# TM1638_10.net
KiCad netlist of a schematic drawn in Altium Designer
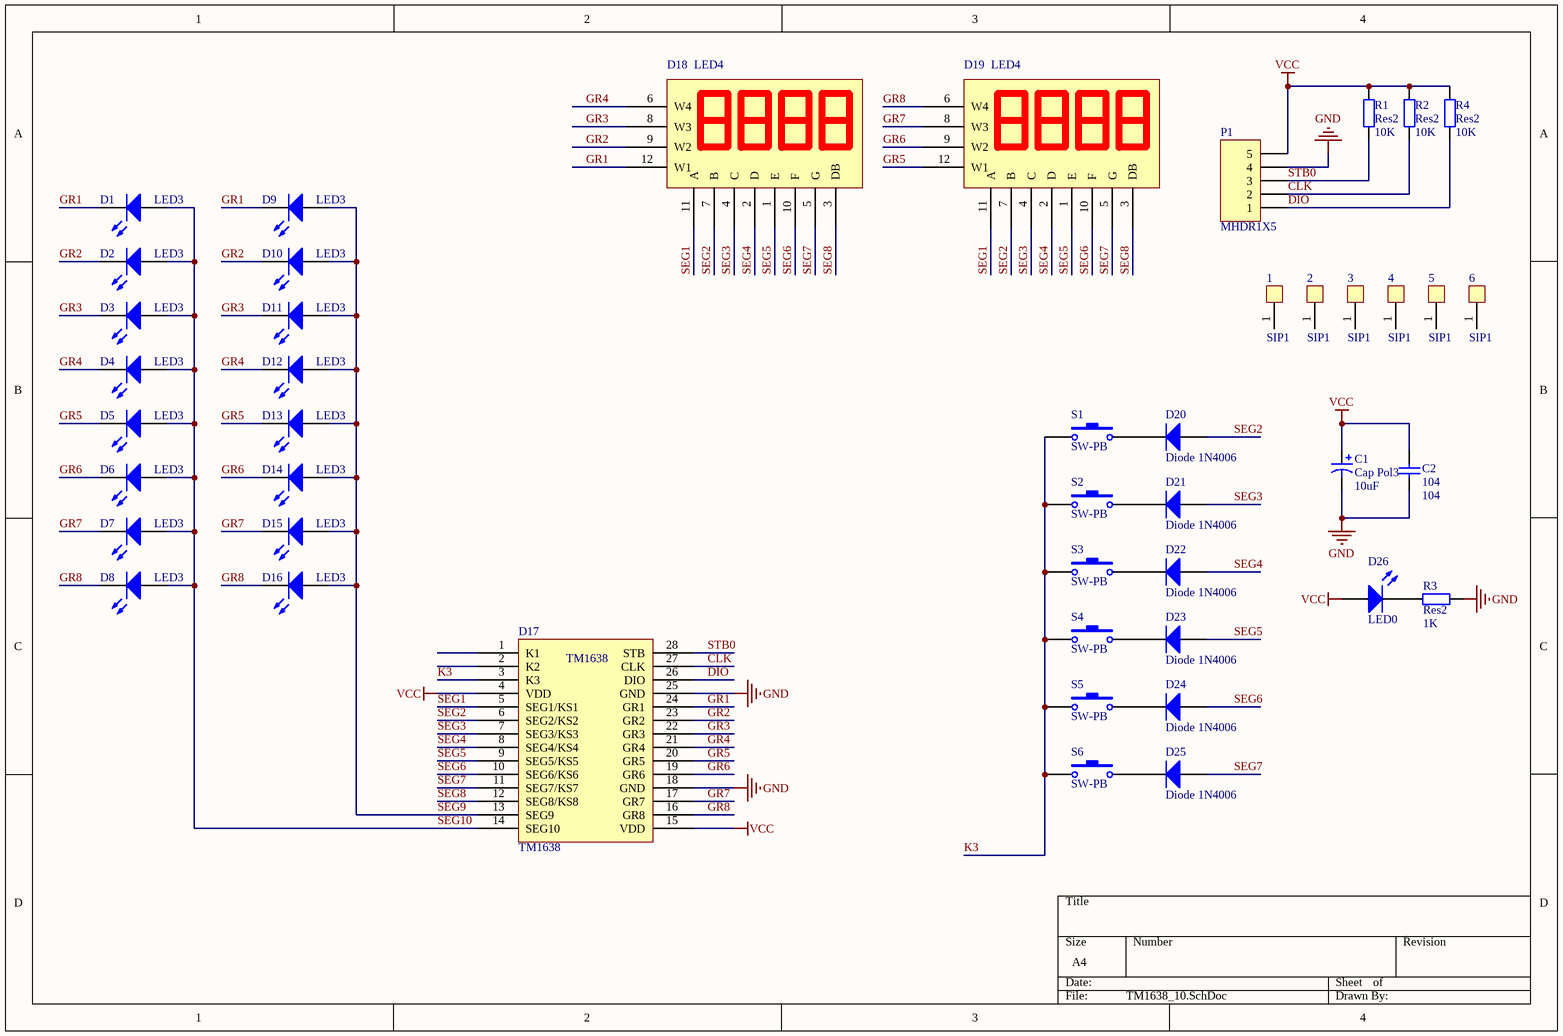
[diagram p0: TM1638_10.SchDoc]

(export (version "E")
  (design (tool "Eeschema 10.0.6"))
  (components
    (comp (ref "1")
      (value "SIP1")
      (footprint "hole")
      (description "Variable Resistor")
      (fields (field (name "PUBLISHER") "Altium Limited"))
      (libsource (lib "jointbar") (part "SIP1"))
    )
    (comp (ref "2")
      (value "SIP1")
      (footprint "hole")
      (description "Variable Resistor")
      (fields (field (name "PUBLISHER") "Altium Limited"))
      (libsource (lib "jointbar") (part "SIP1"))
    )
    (comp (ref "3")
      (value "SIP1")
      (footprint "hole")
      (description "Variable Resistor")
      (fields (field (name "PUBLISHER") "Altium Limited"))
      (libsource (lib "jointbar") (part "SIP1"))
    )
    (comp (ref "4")
      (value "SIP1")
      (footprint "hole")
      (description "Variable Resistor")
      (fields (field (name "PUBLISHER") "Altium Limited"))
      (libsource (lib "jointbar") (part "SIP1"))
    )
    (comp (ref "5")
      (value "SIP1")
      (footprint "hole")
      (description "Variable Resistor")
      (fields (field (name "PUBLISHER") "Altium Limited"))
      (libsource (lib "jointbar") (part "SIP1"))
    )
    (comp (ref "6")
      (value "SIP1")
      (footprint "hole")
      (description "Variable Resistor")
      (fields (field (name "PUBLISHER") "Altium Limited"))
      (libsource (lib "jointbar") (part "SIP1"))
    )
    (comp (ref "C1")
      (value "Cap Pol3")
      (footprint "0805")
      (description "Polarized Capacitor (Surface Mount)")
      (fields (field (name "ALTIUM_VALUE") "10uF") (field (name "PUBLISHER") "Altium Limited"))
      (libsource (lib "Miscellaneous Devices") (part "Cap Pol3"))
    )
    (comp (ref "C2")
      (value "104")
      (footprint "0805")
      (description "Capacitor (Semiconductor SIM Model)")
      (fields (field (name "ALTIUM_VALUE") "104") (field (name "PUBLISHER") "Altium Limited"))
      (libsource (lib "Miscellaneous Devices") (part "Cap Semi"))
    )
    (comp (ref "D1")
      (value "LED3")
      (footprint "LED0")
      (description "Typical BLUE SiC LED")
      (fields (field (name "PUBLISHER") "Altium Limited"))
      (libsource (lib "Miscellaneous Devices") (part "LED3"))
    )
    (comp (ref "D2")
      (value "LED3")
      (footprint "LED0")
      (description "Typical BLUE SiC LED")
      (fields (field (name "PUBLISHER") "Altium Limited"))
      (libsource (lib "Miscellaneous Devices") (part "LED3"))
    )
    (comp (ref "D3")
      (value "LED3")
      (footprint "LED0")
      (description "Typical BLUE SiC LED")
      (fields (field (name "PUBLISHER") "Altium Limited"))
      (libsource (lib "Miscellaneous Devices") (part "LED3"))
    )
    (comp (ref "D4")
      (value "LED3")
      (footprint "LED0")
      (description "Typical BLUE SiC LED")
      (fields (field (name "PUBLISHER") "Altium Limited"))
      (libsource (lib "Miscellaneous Devices") (part "LED3"))
    )
    (comp (ref "D5")
      (value "LED3")
      (footprint "LED0")
      (description "Typical BLUE SiC LED")
      (fields (field (name "PUBLISHER") "Altium Limited"))
      (libsource (lib "Miscellaneous Devices") (part "LED3"))
    )
    (comp (ref "D6")
      (value "LED3")
      (footprint "LED0")
      (description "Typical BLUE SiC LED")
      (fields (field (name "PUBLISHER") "Altium Limited"))
      (libsource (lib "Miscellaneous Devices") (part "LED3"))
    )
    (comp (ref "D7")
      (value "LED3")
      (footprint "LED0")
      (description "Typical BLUE SiC LED")
      (fields (field (name "PUBLISHER") "Altium Limited"))
      (libsource (lib "Miscellaneous Devices") (part "LED3"))
    )
    (comp (ref "D8")
      (value "LED3")
      (footprint "LED0")
      (description "Typical BLUE SiC LED")
      (fields (field (name "PUBLISHER") "Altium Limited"))
      (libsource (lib "Miscellaneous Devices") (part "LED3"))
    )
    (comp (ref "D9")
      (value "LED3")
      (footprint "LED0")
      (description "Typical BLUE SiC LED")
      (fields (field (name "PUBLISHER") "Altium Limited"))
      (libsource (lib "Miscellaneous Devices") (part "LED3"))
    )
    (comp (ref "D10")
      (value "LED3")
      (footprint "LED0")
      (description "Typical BLUE SiC LED")
      (fields (field (name "PUBLISHER") "Altium Limited"))
      (libsource (lib "Miscellaneous Devices") (part "LED3"))
    )
    (comp (ref "D11")
      (value "LED3")
      (footprint "LED0")
      (description "Typical BLUE SiC LED")
      (fields (field (name "PUBLISHER") "Altium Limited"))
      (libsource (lib "Miscellaneous Devices") (part "LED3"))
    )
    (comp (ref "D12")
      (value "LED3")
      (footprint "LED0")
      (description "Typical BLUE SiC LED")
      (fields (field (name "PUBLISHER") "Altium Limited"))
      (libsource (lib "Miscellaneous Devices") (part "LED3"))
    )
    (comp (ref "D13")
      (value "LED3")
      (footprint "LED0")
      (description "Typical BLUE SiC LED")
      (fields (field (name "PUBLISHER") "Altium Limited"))
      (libsource (lib "Miscellaneous Devices") (part "LED3"))
    )
    (comp (ref "D14")
      (value "LED3")
      (footprint "LED0")
      (description "Typical BLUE SiC LED")
      (fields (field (name "PUBLISHER") "Altium Limited"))
      (libsource (lib "Miscellaneous Devices") (part "LED3"))
    )
    (comp (ref "D15")
      (value "LED3")
      (footprint "LED0")
      (description "Typical BLUE SiC LED")
      (fields (field (name "PUBLISHER") "Altium Limited"))
      (libsource (lib "Miscellaneous Devices") (part "LED3"))
    )
    (comp (ref "D16")
      (value "LED3")
      (footprint "LED0")
      (description "Typical BLUE SiC LED")
      (fields (field (name "PUBLISHER") "Altium Limited"))
      (libsource (lib "Miscellaneous Devices") (part "LED3"))
    )
    (comp (ref "D17") (value "TM1638") (footprint "SOP28") (libsource (lib "AD620") (part "TM1638")))
    (comp (ref "D18") (value "LED4") (footprint "LED4") (libsource (lib "AD620") (part "LED_N4")))
    (comp (ref "D19") (value "LED4") (footprint "LED4") (libsource (lib "AD620") (part "LED_N4")))
    (comp (ref "D20")
      (value "Diode 1N4006")
      (footprint "1N4148")
      (description "1 Amp General Purpose Rectifier")
      (fields (field (name "PUBLISHER") "Altium Limited"))
      (libsource (lib "Miscellaneous Devices") (part "Diode 1N4006"))
    )
    (comp (ref "D21")
      (value "Diode 1N4006")
      (footprint "1N4148")
      (description "1 Amp General Purpose Rectifier")
      (fields (field (name "PUBLISHER") "Altium Limited"))
      (libsource (lib "Miscellaneous Devices") (part "Diode 1N4006"))
    )
    (comp (ref "D22")
      (value "Diode 1N4006")
      (footprint "1N4148")
      (description "1 Amp General Purpose Rectifier")
      (fields (field (name "PUBLISHER") "Altium Limited"))
      (libsource (lib "Miscellaneous Devices") (part "Diode 1N4006"))
    )
    (comp (ref "D23")
      (value "Diode 1N4006")
      (footprint "1N4148")
      (description "1 Amp General Purpose Rectifier")
      (fields (field (name "PUBLISHER") "Altium Limited"))
      (libsource (lib "Miscellaneous Devices") (part "Diode 1N4006"))
    )
    (comp (ref "D24")
      (value "Diode 1N4006")
      (footprint "1N4148")
      (description "1 Amp General Purpose Rectifier")
      (fields (field (name "PUBLISHER") "Altium Limited"))
      (libsource (lib "Miscellaneous Devices") (part "Diode 1N4006"))
    )
    (comp (ref "D25")
      (value "Diode 1N4006")
      (footprint "1N4148")
      (description "1 Amp General Purpose Rectifier")
      (fields (field (name "PUBLISHER") "Altium Limited"))
      (libsource (lib "Miscellaneous Devices") (part "Diode 1N4006"))
    )
    (comp (ref "D26")
      (value "LED0")
      (footprint "LED0")
      (description "Typical INFRARED GaAs LED")
      (fields (field (name "PUBLISHER") "Altium Limited"))
      (libsource (lib "Miscellaneous Devices") (part "LED0"))
    )
    (comp (ref "P1")
      (value "MHDR1X5")
      (footprint "CON5")
      (description "Header, 5-Pin")
      (fields (field (name "PUBLISHER") "Altium Limited"))
      (libsource (lib "Miscellaneous Connectors") (part "MHDR1X5"))
    )
    (comp (ref "R1")
      (value "Res2")
      (footprint "0805")
      (description "Resistor")
      (fields (field (name "ALTIUM_VALUE") "10K") (field (name "PUBLISHER") "Altium Limited"))
      (libsource (lib "Miscellaneous Devices") (part "Res2"))
    )
    (comp (ref "R2")
      (value "Res2")
      (footprint "0805")
      (description "Resistor")
      (fields (field (name "ALTIUM_VALUE") "10K") (field (name "PUBLISHER") "Altium Limited"))
      (libsource (lib "Miscellaneous Devices") (part "Res2"))
    )
    (comp (ref "R3")
      (value "Res2")
      (footprint "0805")
      (description "Resistor")
      (fields (field (name "ALTIUM_VALUE") "1K") (field (name "PUBLISHER") "Altium Limited"))
      (libsource (lib "") (part "Res2_1"))
    )
    (comp (ref "R4")
      (value "Res2")
      (footprint "0805")
      (description "Resistor")
      (fields (field (name "ALTIUM_VALUE") "10K") (field (name "PUBLISHER") "Altium Limited"))
      (libsource (lib "Miscellaneous Devices") (part "Res2"))
    )
    (comp (ref "S1")
      (value "SW-PB")
      (footprint "key")
      (description "Switch")
      (fields (field (name "PUBLISHER") "Altium Limited"))
      (libsource (lib "Miscellaneous Devices") (part "SW-PB"))
    )
    (comp (ref "S2")
      (value "SW-PB")
      (footprint "key")
      (description "Switch")
      (fields (field (name "PUBLISHER") "Altium Limited"))
      (libsource (lib "Miscellaneous Devices") (part "SW-PB"))
    )
    (comp (ref "S3")
      (value "SW-PB")
      (footprint "key")
      (description "Switch")
      (fields (field (name "PUBLISHER") "Altium Limited"))
      (libsource (lib "Miscellaneous Devices") (part "SW-PB"))
    )
    (comp (ref "S4")
      (value "SW-PB")
      (footprint "key")
      (description "Switch")
      (fields (field (name "PUBLISHER") "Altium Limited"))
      (libsource (lib "Miscellaneous Devices") (part "SW-PB"))
    )
    (comp (ref "S5")
      (value "SW-PB")
      (footprint "key")
      (description "Switch")
      (fields (field (name "PUBLISHER") "Altium Limited"))
      (libsource (lib "Miscellaneous Devices") (part "SW-PB"))
    )
    (comp (ref "S6")
      (value "SW-PB")
      (footprint "key")
      (description "Switch")
      (fields (field (name "PUBLISHER") "Altium Limited"))
      (libsource (lib "Miscellaneous Devices") (part "SW-PB"))
    )
  )
  (nets
    (net (code "1") (name "/CLK") (class "Default")
      (node (ref "D17") (pin "27") (pinfunction "CLK_27") (pintype "passive"))
      (node (ref "P1") (pin "2") (pinfunction "2_2") (pintype "passive"))
      (node (ref "R2") (pin "1") (pinfunction "1_1") (pintype "passive"))
    )
    (net (code "2") (name "/DIO") (class "Default")
      (node (ref "D17") (pin "26") (pinfunction "DIO_26") (pintype "passive"))
      (node (ref "P1") (pin "1") (pinfunction "1_1") (pintype "passive"))
      (node (ref "R4") (pin "1") (pinfunction "1_1") (pintype "passive"))
    )
    (net (code "3") (name "/GR1") (class "Default")
      (node (ref "D1") (pin "2") (pinfunction "K_2") (pintype "passive"))
      (node (ref "D17") (pin "24") (pinfunction "GR1_24") (pintype "passive"))
      (node (ref "D18") (pin "12") (pinfunction "W1_12") (pintype "passive"))
      (node (ref "D9") (pin "2") (pinfunction "K_2") (pintype "passive"))
    )
    (net (code "4") (name "/GR2") (class "Default")
      (node (ref "D10") (pin "2") (pinfunction "K_2") (pintype "passive"))
      (node (ref "D17") (pin "23") (pinfunction "GR2_23") (pintype "passive"))
      (node (ref "D18") (pin "9") (pinfunction "W2_9") (pintype "passive"))
      (node (ref "D2") (pin "2") (pinfunction "K_2") (pintype "passive"))
    )
    (net (code "5") (name "/GR3") (class "Default")
      (node (ref "D11") (pin "2") (pinfunction "K_2") (pintype "passive"))
      (node (ref "D17") (pin "22") (pinfunction "GR3_22") (pintype "passive"))
      (node (ref "D18") (pin "8") (pinfunction "W3_8") (pintype "passive"))
      (node (ref "D3") (pin "2") (pinfunction "K_2") (pintype "passive"))
    )
    (net (code "6") (name "/GR4") (class "Default")
      (node (ref "D12") (pin "2") (pinfunction "K_2") (pintype "passive"))
      (node (ref "D17") (pin "21") (pinfunction "GR4_21") (pintype "passive"))
      (node (ref "D18") (pin "6") (pinfunction "W4_6") (pintype "passive"))
      (node (ref "D4") (pin "2") (pinfunction "K_2") (pintype "passive"))
    )
    (net (code "7") (name "/GR5") (class "Default")
      (node (ref "D13") (pin "2") (pinfunction "K_2") (pintype "passive"))
      (node (ref "D17") (pin "20") (pinfunction "GR5_20") (pintype "passive"))
      (node (ref "D19") (pin "12") (pinfunction "W1_12") (pintype "passive"))
      (node (ref "D5") (pin "2") (pinfunction "K_2") (pintype "passive"))
    )
    (net (code "8") (name "/GR6") (class "Default")
      (node (ref "D14") (pin "2") (pinfunction "K_2") (pintype "passive"))
      (node (ref "D17") (pin "19") (pinfunction "GR6_19") (pintype "passive"))
      (node (ref "D19") (pin "9") (pinfunction "W2_9") (pintype "passive"))
      (node (ref "D6") (pin "2") (pinfunction "K_2") (pintype "passive"))
    )
    (net (code "9") (name "/GR7") (class "Default")
      (node (ref "D15") (pin "2") (pinfunction "K_2") (pintype "passive"))
      (node (ref "D17") (pin "17") (pinfunction "GR7_17") (pintype "passive"))
      (node (ref "D19") (pin "8") (pinfunction "W3_8") (pintype "passive"))
      (node (ref "D7") (pin "2") (pinfunction "K_2") (pintype "passive"))
    )
    (net (code "10") (name "/GR8") (class "Default")
      (node (ref "D16") (pin "2") (pinfunction "K_2") (pintype "passive"))
      (node (ref "D17") (pin "16") (pinfunction "GR8_16") (pintype "passive"))
      (node (ref "D19") (pin "6") (pinfunction "W4_6") (pintype "passive"))
      (node (ref "D8") (pin "2") (pinfunction "K_2") (pintype "passive"))
    )
    (net (code "11") (name "/K3") (class "Default")
      (node (ref "D17") (pin "3") (pinfunction "K3_3") (pintype "passive"))
      (node (ref "S1") (pin "1") (pinfunction "1_1") (pintype "passive"))
      (node (ref "S2") (pin "1") (pinfunction "1_1") (pintype "passive"))
      (node (ref "S3") (pin "1") (pinfunction "1_1") (pintype "passive"))
      (node (ref "S4") (pin "1") (pinfunction "1_1") (pintype "passive"))
      (node (ref "S5") (pin "1") (pinfunction "1_1") (pintype "passive"))
      (node (ref "S6") (pin "1") (pinfunction "1_1") (pintype "passive"))
    )
    (net (code "12") (name "/SEG1") (class "Default")
      (node (ref "D17") (pin "5") (pinfunction "SEG1/KS1_5") (pintype "passive"))
      (node (ref "D18") (pin "11") (pinfunction "A_11") (pintype "passive"))
      (node (ref "D19") (pin "11") (pinfunction "A_11") (pintype "passive"))
    )
    (net (code "13") (name "/SEG2") (class "Default")
      (node (ref "D17") (pin "6") (pinfunction "SEG2/KS2_6") (pintype "passive"))
      (node (ref "D18") (pin "7") (pinfunction "B_7") (pintype "passive"))
      (node (ref "D19") (pin "7") (pinfunction "B_7") (pintype "passive"))
      (node (ref "D20") (pin "1") (pinfunction "A_1") (pintype "passive"))
    )
    (net (code "14") (name "/SEG3") (class "Default")
      (node (ref "D17") (pin "7") (pinfunction "SEG3/KS3_7") (pintype "passive"))
      (node (ref "D18") (pin "4") (pinfunction "C_4") (pintype "passive"))
      (node (ref "D19") (pin "4") (pinfunction "C_4") (pintype "passive"))
      (node (ref "D21") (pin "1") (pinfunction "A_1") (pintype "passive"))
    )
    (net (code "15") (name "/SEG4") (class "Default")
      (node (ref "D17") (pin "8") (pinfunction "SEG4/KS4_8") (pintype "passive"))
      (node (ref "D18") (pin "2") (pinfunction "D_2") (pintype "passive"))
      (node (ref "D19") (pin "2") (pinfunction "D_2") (pintype "passive"))
      (node (ref "D22") (pin "1") (pinfunction "A_1") (pintype "passive"))
    )
    (net (code "16") (name "/SEG5") (class "Default")
      (node (ref "D17") (pin "9") (pinfunction "SEG5/KS5_9") (pintype "passive"))
      (node (ref "D18") (pin "1") (pinfunction "E_1") (pintype "passive"))
      (node (ref "D19") (pin "1") (pinfunction "E_1") (pintype "passive"))
      (node (ref "D23") (pin "1") (pinfunction "A_1") (pintype "passive"))
    )
    (net (code "17") (name "/SEG6") (class "Default")
      (node (ref "D17") (pin "10") (pinfunction "SEG6/KS6_10") (pintype "passive"))
      (node (ref "D18") (pin "10") (pinfunction "F_10") (pintype "passive"))
      (node (ref "D19") (pin "10") (pinfunction "F_10") (pintype "passive"))
      (node (ref "D24") (pin "1") (pinfunction "A_1") (pintype "passive"))
    )
    (net (code "18") (name "/SEG7") (class "Default")
      (node (ref "D17") (pin "11") (pinfunction "SEG7/KS7_11") (pintype "passive"))
      (node (ref "D18") (pin "5") (pinfunction "G_5") (pintype "passive"))
      (node (ref "D19") (pin "5") (pinfunction "G_5") (pintype "passive"))
      (node (ref "D25") (pin "1") (pinfunction "A_1") (pintype "passive"))
    )
    (net (code "19") (name "/SEG8") (class "Default")
      (node (ref "D17") (pin "12") (pinfunction "SEG8/KS8_12") (pintype "passive"))
      (node (ref "D18") (pin "3") (pinfunction "DB_3") (pintype "passive"))
      (node (ref "D19") (pin "3") (pinfunction "DB_3") (pintype "passive"))
    )
    (net (code "20") (name "/SEG9") (class "Default")
      (node (ref "D10") (pin "1") (pinfunction "A_1") (pintype "passive"))
      (node (ref "D11") (pin "1") (pinfunction "A_1") (pintype "passive"))
      (node (ref "D12") (pin "1") (pinfunction "A_1") (pintype "passive"))
      (node (ref "D13") (pin "1") (pinfunction "A_1") (pintype "passive"))
      (node (ref "D14") (pin "1") (pinfunction "A_1") (pintype "passive"))
      (node (ref "D15") (pin "1") (pinfunction "A_1") (pintype "passive"))
      (node (ref "D16") (pin "1") (pinfunction "A_1") (pintype "passive"))
      (node (ref "D17") (pin "13") (pinfunction "SEG9_13") (pintype "passive"))
      (node (ref "D9") (pin "1") (pinfunction "A_1") (pintype "passive"))
    )
    (net (code "21") (name "/SEG10") (class "Default")
      (node (ref "D1") (pin "1") (pinfunction "A_1") (pintype "passive"))
      (node (ref "D17") (pin "14") (pinfunction "SEG10_14") (pintype "passive"))
      (node (ref "D2") (pin "1") (pinfunction "A_1") (pintype "passive"))
      (node (ref "D3") (pin "1") (pinfunction "A_1") (pintype "passive"))
      (node (ref "D4") (pin "1") (pinfunction "A_1") (pintype "passive"))
      (node (ref "D5") (pin "1") (pinfunction "A_1") (pintype "passive"))
      (node (ref "D6") (pin "1") (pinfunction "A_1") (pintype "passive"))
      (node (ref "D7") (pin "1") (pinfunction "A_1") (pintype "passive"))
      (node (ref "D8") (pin "1") (pinfunction "A_1") (pintype "passive"))
    )
    (net (code "22") (name "/STB0") (class "Default")
      (node (ref "D17") (pin "28") (pinfunction "STB_28") (pintype "passive"))
      (node (ref "P1") (pin "3") (pinfunction "3_3") (pintype "passive"))
      (node (ref "R1") (pin "1") (pinfunction "1_1") (pintype "passive"))
    )
    (net (code "23") (name "GND") (class "Default")
      (node (ref "C1") (pin "2") (pinfunction "2_2") (pintype "passive"))
      (node (ref "C2") (pin "1") (pinfunction "1_1") (pintype "passive"))
      (node (ref "D17") (pin "18") (pinfunction "GND_18") (pintype "passive"))
      (node (ref "D17") (pin "25") (pinfunction "GND_25") (pintype "passive"))
      (node (ref "P1") (pin "4") (pinfunction "4_4") (pintype "passive"))
      (node (ref "R3") (pin "1") (pinfunction "1_1") (pintype "passive"))
    )
    (net (code "24") (name "Net-(D20-K)") (class "Default")
      (node (ref "D20") (pin "2") (pinfunction "K_2") (pintype "passive"))
      (node (ref "S1") (pin "2") (pinfunction "2_2") (pintype "passive"))
    )
    (net (code "25") (name "Net-(D21-K)") (class "Default")
      (node (ref "D21") (pin "2") (pinfunction "K_2") (pintype "passive"))
      (node (ref "S2") (pin "2") (pinfunction "2_2") (pintype "passive"))
    )
    (net (code "26") (name "Net-(D22-K)") (class "Default")
      (node (ref "D22") (pin "2") (pinfunction "K_2") (pintype "passive"))
      (node (ref "S3") (pin "2") (pinfunction "2_2") (pintype "passive"))
    )
    (net (code "27") (name "Net-(D23-K)") (class "Default")
      (node (ref "D23") (pin "2") (pinfunction "K_2") (pintype "passive"))
      (node (ref "S4") (pin "2") (pinfunction "2_2") (pintype "passive"))
    )
    (net (code "28") (name "Net-(D24-K)") (class "Default")
      (node (ref "D24") (pin "2") (pinfunction "K_2") (pintype "passive"))
      (node (ref "S5") (pin "2") (pinfunction "2_2") (pintype "passive"))
    )
    (net (code "29") (name "Net-(D25-K)") (class "Default")
      (node (ref "D25") (pin "2") (pinfunction "K_2") (pintype "passive"))
      (node (ref "S6") (pin "2") (pinfunction "2_2") (pintype "passive"))
    )
    (net (code "30") (name "Net-(D26-K)") (class "Default")
      (node (ref "D26") (pin "2") (pinfunction "K_2") (pintype "passive"))
      (node (ref "R3") (pin "2") (pinfunction "2_2") (pintype "passive"))
    )
    (net (code "31") (name "VCC") (class "Default")
      (node (ref "C1") (pin "1") (pinfunction "1_1") (pintype "passive"))
      (node (ref "C2") (pin "2") (pinfunction "2_2") (pintype "passive"))
      (node (ref "D17") (pin "15") (pinfunction "VDD_15") (pintype "passive"))
      (node (ref "D17") (pin "4") (pinfunction "VDD_4") (pintype "passive"))
      (node (ref "D26") (pin "1") (pinfunction "A_1") (pintype "passive"))
      (node (ref "P1") (pin "5") (pinfunction "5_5") (pintype "passive"))
      (node (ref "R1") (pin "2") (pinfunction "2_2") (pintype "passive"))
      (node (ref "R2") (pin "2") (pinfunction "2_2") (pintype "passive"))
      (node (ref "R4") (pin "2") (pinfunction "2_2") (pintype "passive"))
    )
    (net (code "32") (name "unconnected-(1-Pad1)") (class "Default")
      (node (ref "1") (pin "1") (pinfunction "1_1") (pintype "passive"))
    )
    (net (code "33") (name "unconnected-(2-Pad1)") (class "Default")
      (node (ref "2") (pin "1") (pinfunction "1_1") (pintype "passive"))
    )
    (net (code "34") (name "unconnected-(3-Pad1)") (class "Default")
      (node (ref "3") (pin "1") (pinfunction "1_1") (pintype "passive"))
    )
    (net (code "35") (name "unconnected-(4-Pad1)") (class "Default")
      (node (ref "4") (pin "1") (pinfunction "1_1") (pintype "passive"))
    )
    (net (code "36") (name "unconnected-(5-Pad1)") (class "Default")
      (node (ref "5") (pin "1") (pinfunction "1_1") (pintype "passive"))
    )
    (net (code "37") (name "unconnected-(6-Pad1)") (class "Default")
      (node (ref "6") (pin "1") (pinfunction "1_1") (pintype "passive"))
    )
    (net (code "38") (name "unconnected-(D17-K1-Pad1)") (class "Default")
      (node (ref "D17") (pin "1") (pinfunction "K1_1") (pintype "passive"))
    )
    (net (code "39") (name "unconnected-(D17-K2-Pad2)") (class "Default")
      (node (ref "D17") (pin "2") (pinfunction "K2_2") (pintype "passive"))
    )
  )
)
